# LED_Indicators.net
KiCad netlist of a schematic drawn in Altium Designer
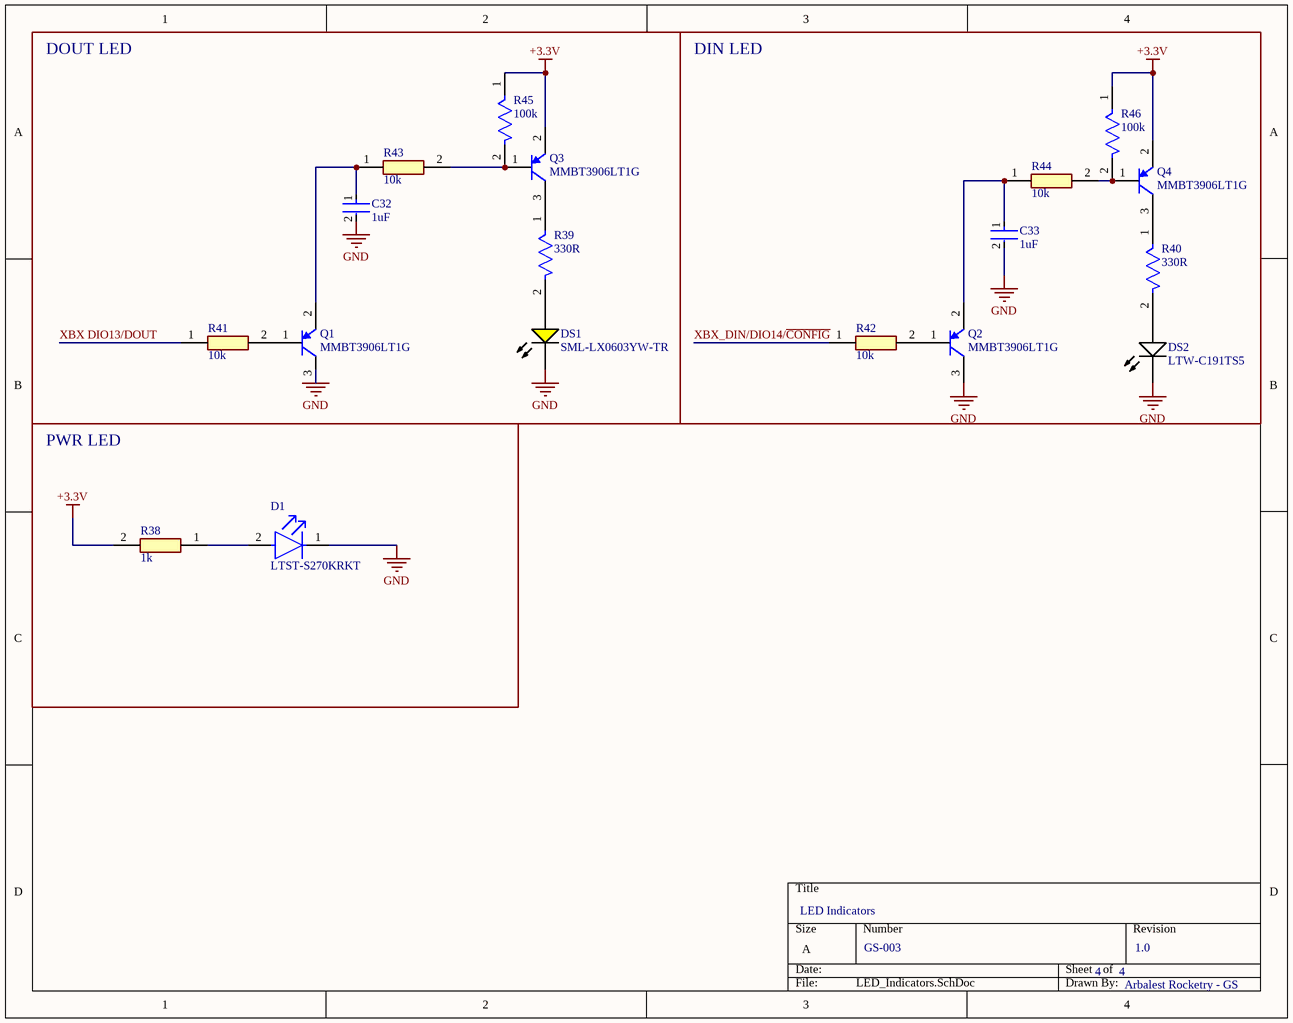
[diagram p0: LED_Indicators.SchDoc]

(export (version "E")
  (design (tool "Eeschema 10.0.6"))
  (components
    (comp (ref "C32")
      (value "1uF")
      (footprint "FP-0603-L_1_6_0_1-W_0_8_0-IPC_A")
      (description "None")
      (fields (field (name "TOLERANCE") "10%"))
      (libsource (lib "Altium Content Vault") (part "02cd4be3c70576c341d710602a673aa"))
    )
    (comp (ref "C33")
      (value "1uF")
      (footprint "FP-0603-L_1_6_0_1-W_0_8_0-IPC_A")
      (description "None")
      (fields (field (name "TOLERANCE") "10%"))
      (libsource (lib "Altium Content Vault") (part "02cd4be3c70576c341d710602a673aa"))
    )
    (comp (ref "D1")
      (value "LTST-S270KRKT")
      (footprint "FP-LTST-S270KRKT-MFG")
      (description "LED RED CLEAR CHIP SMD R/A")
      (libsource (lib "Altium Content Vault") (part "8706943c75ba83719d021d2fdc84c58"))
    )
    (comp (ref "DS1")
      (value "SML-LX0603YW-TR")
      (footprint "LUMX-SML-LX0603_V")
      (fields (field (name "MANUFACTURER") "Lumex"))
      (libsource (lib "Altium Content Vault") (part "LED-YELLOW-AK-2"))
    )
    (comp (ref "DS2")
      (value "LTW-C191TS5")
      (footprint "LTST-LTW-C191TS5_V")
      (description "LED Uni-Color White, 70 mW, 20 mA, -20 to 80 degC, 2-Pin SMD, RoHS, Tape and Reel")
      (fields (field (name "TOLERANCE") "1%"))
      (libsource (lib "Altium Content Vault") (part "LED-WHITE-AK-2"))
    )
    (comp (ref "Q1")
      (value "MMBT3906LT1G")
      (footprint "ONSC-SOT-23-3-318-08_V")
      (description "General Purpose Transistor, PNP Silicon, 3-Pin SOT-23, Pb-Free, Tape and Reel")
      (fields (field (name "MANUFACTURER") "On Semiconductor"))
      (libsource (lib "Altium Content Vault") (part "ONSC-PNP-B1E2C3-3"))
    )
    (comp (ref "Q2")
      (value "MMBT3906LT1G")
      (footprint "ONSC-SOT-23-3-318-08_V")
      (description "General Purpose Transistor, PNP Silicon, 3-Pin SOT-23, Pb-Free, Tape and Reel")
      (fields (field (name "MANUFACTURER") "On Semiconductor"))
      (libsource (lib "Altium Content Vault") (part "ONSC-PNP-B1E2C3-3"))
    )
    (comp (ref "Q3")
      (value "MMBT3906LT1G")
      (footprint "ONSC-SOT-23-3-318-08_V")
      (description "General Purpose Transistor, PNP Silicon, 3-Pin SOT-23, Pb-Free, Tape and Reel")
      (fields (field (name "MANUFACTURER") "On Semiconductor"))
      (libsource (lib "Altium Content Vault") (part "ONSC-PNP-B1E2C3-3"))
    )
    (comp (ref "Q4")
      (value "MMBT3906LT1G")
      (footprint "ONSC-SOT-23-3-318-08_V")
      (description "General Purpose Transistor, PNP Silicon, 3-Pin SOT-23, Pb-Free, Tape and Reel")
      (fields (field (name "MANUFACTURER") "On Semiconductor"))
      (libsource (lib "Altium Content Vault") (part "ONSC-PNP-B1E2C3-3"))
    )
    (comp (ref "R38")
      (value "1k")
      (footprint "SamacSys:RESC1608X55N")
      (description "Resistor")
      (fields
        (field (name "MANUFACTURER_PART_NUMBER") "CR0603-JW-102ELF")
        (field (name "MOUSER PART NUMBER") "652-CR0603-JW-102ELF")
      )
      (libsource (lib "*") (part "CR0603-JW-102ELF"))
    )
    (comp (ref "R39")
      (value "330R")
      (footprint "FP-RMCF0603-MFG")
      (description "330Ω ±5% 0.1W 0603 Thick Film Chip Resistor AEC-Q200 compliant")
      (fields (field (name "TOLERANCE") "5%"))
      (libsource (lib "Altium Content Vault") (part "1029c3af85768c4190bb7ad29bc67b5"))
    )
    (comp (ref "R40")
      (value "330R")
      (footprint "FP-RMCF0603-MFG")
      (description "330Ω ±5% 0.1W 0603 Thick Film Chip Resistor AEC-Q200 compliant")
      (fields (field (name "TOLERANCE") "5%"))
      (libsource (lib "Altium Content Vault") (part "1029c3af85768c4190bb7ad29bc67b5"))
    )
    (comp (ref "R41")
      (value "10k")
      (footprint "SamacSys:RESC1608X55N")
      (description "Resistor")
      (fields
        (field (name "MANUFACTURER_PART_NUMBER") "CR0603-FX-1002ELF")
        (field (name "MOUSER PART NUMBER") "652-CR0603FX-1002ELF")
      )
      (libsource (lib "*") (part "CR0603-FX-1002ELF"))
    )
    (comp (ref "R42")
      (value "10k")
      (footprint "SamacSys:RESC1608X55N")
      (description "Resistor")
      (fields
        (field (name "MANUFACTURER_PART_NUMBER") "CR0603-FX-1002ELF")
        (field (name "MOUSER PART NUMBER") "652-CR0603FX-1002ELF")
      )
      (libsource (lib "*") (part "CR0603-FX-1002ELF"))
    )
    (comp (ref "R43")
      (value "10k")
      (footprint "SamacSys:RESC1608X55N")
      (description "Resistor")
      (fields
        (field (name "MANUFACTURER_PART_NUMBER") "CR0603-FX-1002ELF")
        (field (name "MOUSER PART NUMBER") "652-CR0603FX-1002ELF")
      )
      (libsource (lib "*") (part "CR0603-FX-1002ELF"))
    )
    (comp (ref "R44")
      (value "10k")
      (footprint "SamacSys:RESC1608X55N")
      (description "Resistor")
      (fields
        (field (name "MANUFACTURER_PART_NUMBER") "CR0603-FX-1002ELF")
        (field (name "MOUSER PART NUMBER") "652-CR0603FX-1002ELF")
      )
      (libsource (lib "*") (part "CR0603-FX-1002ELF"))
    )
    (comp (ref "R45")
      (value "100k")
      (footprint "FP-MCT0603-IPC_A")
      (description "RES SMD 100 OHM 1% 1/8W 0603")
      (fields (field (name "TOLERANCE") "0.5%"))
      (libsource (lib "Altium Content Vault") (part "1029c3af85768c4190bb7ad29bc67b5"))
    )
    (comp (ref "R46")
      (value "100k")
      (footprint "FP-MCT0603-IPC_A")
      (description "RES SMD 100 OHM 1% 1/8W 0603")
      (fields (field (name "TOLERANCE") "0.5%"))
      (libsource (lib "Altium Content Vault") (part "1029c3af85768c4190bb7ad29bc67b5"))
    )
  )
  (nets
    (net (code "1") (name "+3.3V") (class "Default")
      (node (ref "Q3") (pin "2") (pinfunction "E_2") (pintype "passive"))
      (node (ref "Q4") (pin "2") (pinfunction "E_2") (pintype "passive"))
      (node (ref "R38") (pin "2") (pinfunction "2_2") (pintype "passive"))
      (node (ref "R45") (pin "1") (pinfunction "1_1") (pintype "passive"))
      (node (ref "R46") (pin "1") (pinfunction "1_1") (pintype "passive"))
    )
    (net (code "2") (name "/XBX DIO13{slash}DOUT") (class "Default")
      (node (ref "R41") (pin "1") (pinfunction "1_1") (pintype "passive"))
    )
    (net (code "3") (name "/XBX_DIN{slash}DIO14{slash}~{CONFIG}") (class "Default")
      (node (ref "R42") (pin "1") (pinfunction "1_1") (pintype "passive"))
    )
    (net (code "4") (name "GND") (class "Default")
      (node (ref "C32") (pin "2") (pinfunction "2_2") (pintype "passive"))
      (node (ref "C33") (pin "2") (pinfunction "2_2") (pintype "passive"))
      (node (ref "D1") (pin "1") (pinfunction "C_1") (pintype "passive"))
      (node (ref "DS1") (pin "2") (pinfunction "K_2") (pintype "passive"))
      (node (ref "DS2") (pin "2") (pinfunction "K_2") (pintype "passive"))
      (node (ref "Q1") (pin "3") (pinfunction "C_3") (pintype "passive"))
      (node (ref "Q2") (pin "3") (pinfunction "C_3") (pintype "passive"))
    )
    (net (code "5") (name "Net-(D1-A)") (class "Default")
      (node (ref "D1") (pin "2") (pinfunction "A_2") (pintype "passive"))
      (node (ref "R38") (pin "1") (pinfunction "1_1") (pintype "passive"))
    )
    (net (code "6") (name "Net-(DS1-A)") (class "Default")
      (node (ref "DS1") (pin "1") (pinfunction "A_1") (pintype "passive"))
      (node (ref "R39") (pin "2") (pinfunction "2_2") (pintype "passive"))
    )
    (net (code "7") (name "Net-(DS2-A)") (class "Default")
      (node (ref "DS2") (pin "1") (pinfunction "A_1") (pintype "passive"))
      (node (ref "R40") (pin "2") (pinfunction "2_2") (pintype "passive"))
    )
    (net (code "8") (name "Net-(Q1-B)") (class "Default")
      (node (ref "Q1") (pin "1") (pinfunction "B_1") (pintype "passive"))
      (node (ref "R41") (pin "2") (pinfunction "2_2") (pintype "passive"))
    )
    (net (code "9") (name "Net-(Q1-E)") (class "Default")
      (node (ref "C32") (pin "1") (pinfunction "1_1") (pintype "passive"))
      (node (ref "Q1") (pin "2") (pinfunction "E_2") (pintype "passive"))
      (node (ref "R43") (pin "1") (pinfunction "1_1") (pintype "passive"))
    )
    (net (code "10") (name "Net-(Q2-B)") (class "Default")
      (node (ref "Q2") (pin "1") (pinfunction "B_1") (pintype "passive"))
      (node (ref "R42") (pin "2") (pinfunction "2_2") (pintype "passive"))
    )
    (net (code "11") (name "Net-(Q2-E)") (class "Default")
      (node (ref "C33") (pin "1") (pinfunction "1_1") (pintype "passive"))
      (node (ref "Q2") (pin "2") (pinfunction "E_2") (pintype "passive"))
      (node (ref "R44") (pin "1") (pinfunction "1_1") (pintype "passive"))
    )
    (net (code "12") (name "Net-(Q3-B)") (class "Default")
      (node (ref "Q3") (pin "1") (pinfunction "B_1") (pintype "passive"))
      (node (ref "R43") (pin "2") (pinfunction "2_2") (pintype "passive"))
      (node (ref "R45") (pin "2") (pinfunction "2_2") (pintype "passive"))
    )
    (net (code "13") (name "Net-(Q3-C)") (class "Default")
      (node (ref "Q3") (pin "3") (pinfunction "C_3") (pintype "passive"))
      (node (ref "R39") (pin "1") (pinfunction "1_1") (pintype "passive"))
    )
    (net (code "14") (name "Net-(Q4-B)") (class "Default")
      (node (ref "Q4") (pin "1") (pinfunction "B_1") (pintype "passive"))
      (node (ref "R44") (pin "2") (pinfunction "2_2") (pintype "passive"))
      (node (ref "R46") (pin "2") (pinfunction "2_2") (pintype "passive"))
    )
    (net (code "15") (name "Net-(Q4-C)") (class "Default")
      (node (ref "Q4") (pin "3") (pinfunction "C_3") (pintype "passive"))
      (node (ref "R40") (pin "1") (pinfunction "1_1") (pintype "passive"))
    )
  )
)
